# shield.net
KiCad netlist of a schematic drawn in EAGLE
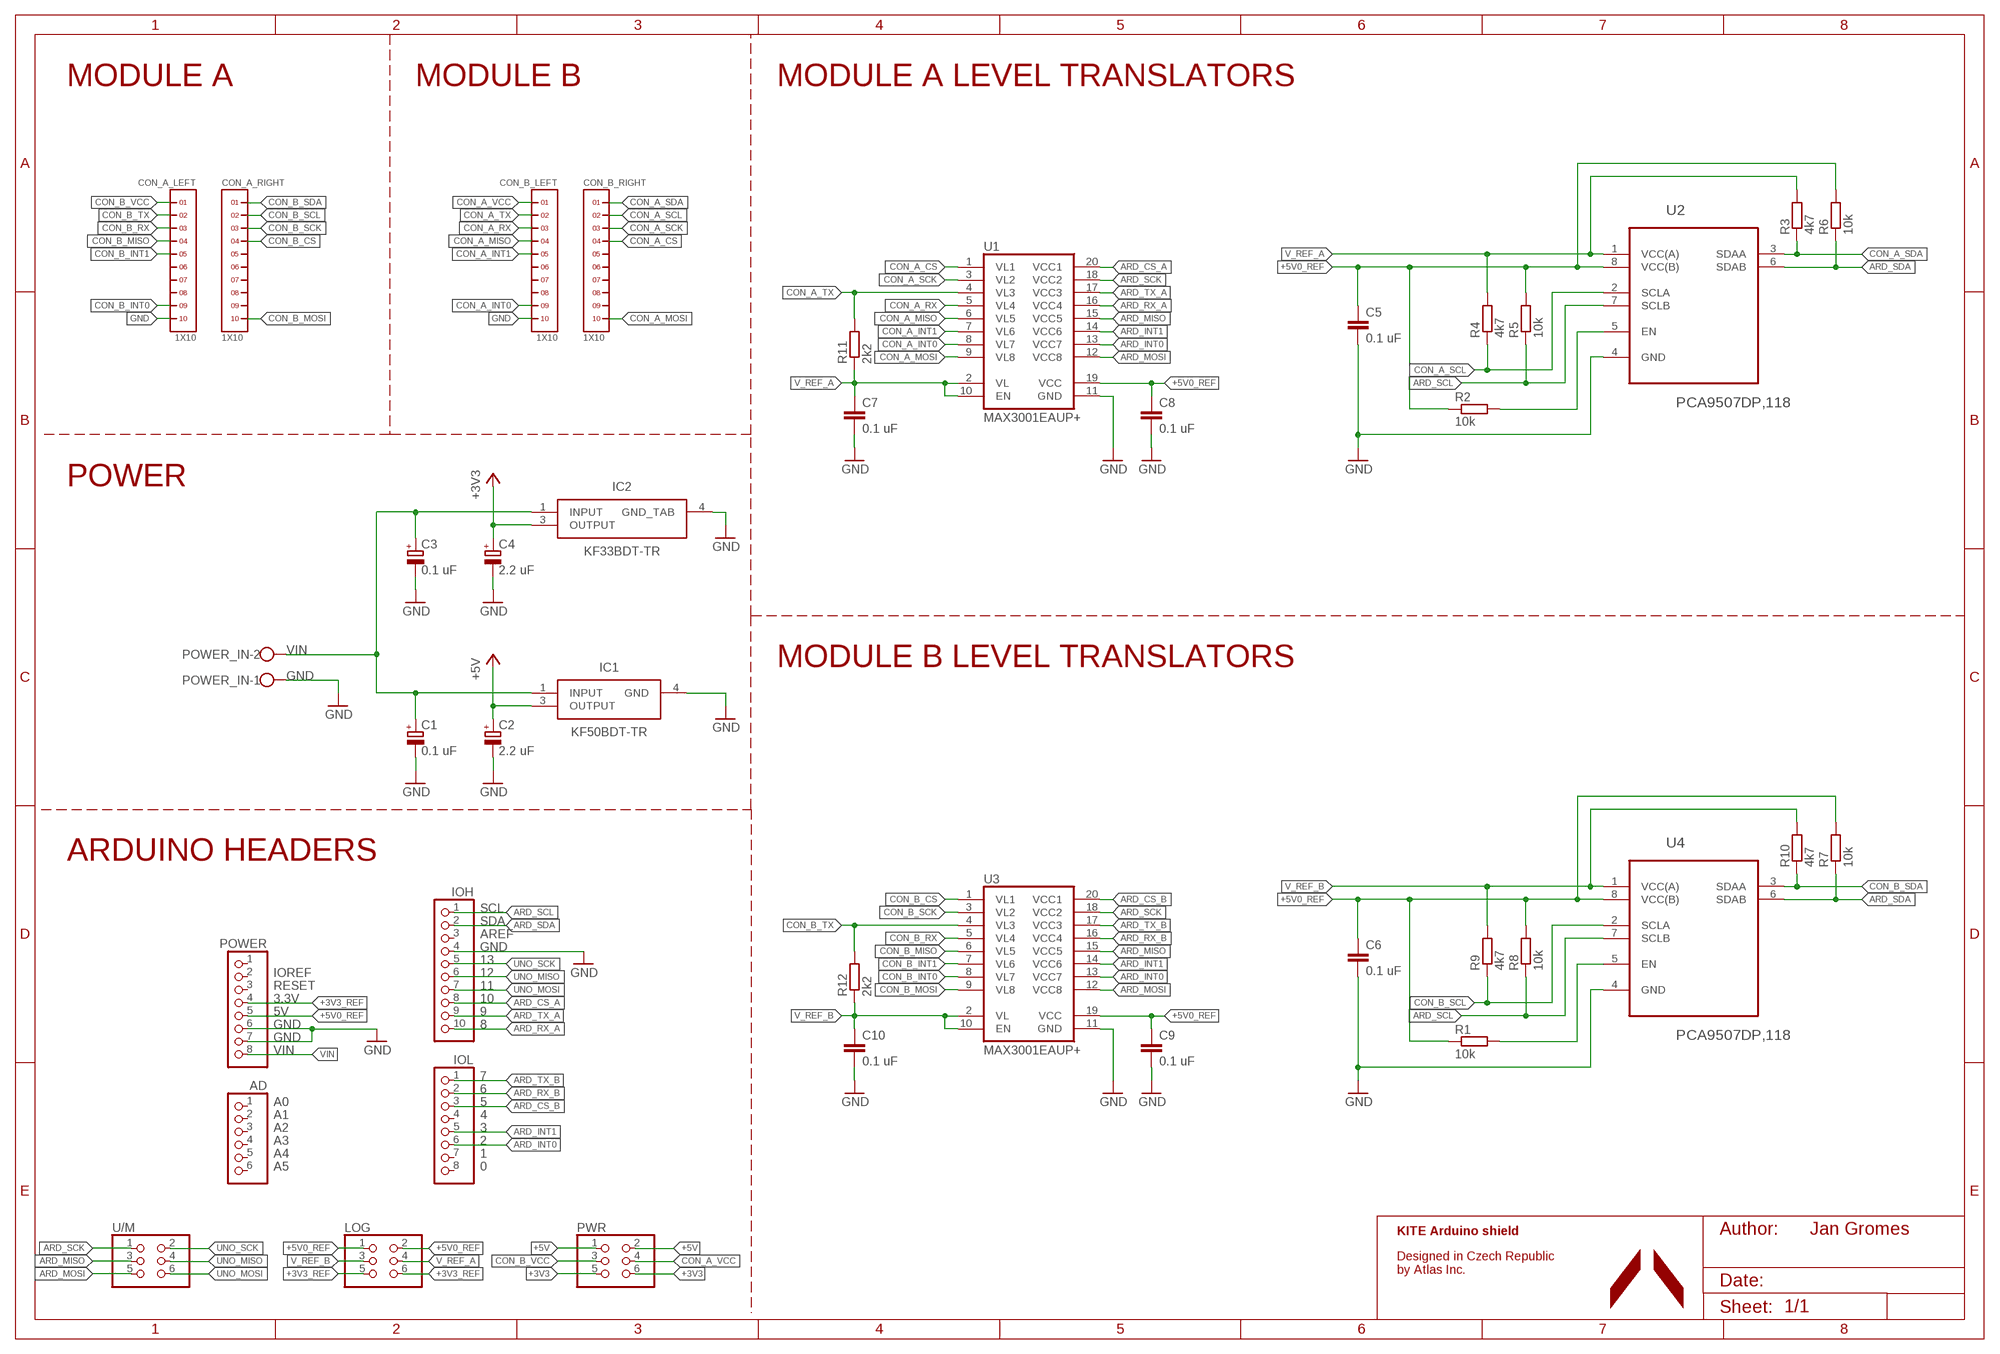
[diagram p0: schematic, sheet 1]

(export (version "E")
  (design (tool "Eeschema 10.0.6"))
  (components
    (comp (ref "AD")
      (value "PINHD-1X6")
      (footprint "eagle-import:1X06")
      (libsource (lib "eagle-import") (part "PINHD-1X6"))
    )
    (comp (ref "C1")
      (value "0.1 uF")
      (footprint "eagle-import:SMC_A")
      (libsource (lib "eagle-import") (part "CPOL-EUSMCA"))
    )
    (comp (ref "C2")
      (value "2.2 uF")
      (footprint "eagle-import:SMC_A")
      (libsource (lib "eagle-import") (part "CPOL-EUSMCA"))
    )
    (comp (ref "C3")
      (value "0.1 uF")
      (footprint "eagle-import:SMC_A")
      (libsource (lib "eagle-import") (part "CPOL-EUSMCA"))
    )
    (comp (ref "C4")
      (value "2.2 uF")
      (footprint "eagle-import:SMC_A")
      (libsource (lib "eagle-import") (part "CPOL-EUSMCA"))
    )
    (comp (ref "C5")
      (value "0.1 uF")
      (footprint "eagle-import:C0603")
      (libsource (lib "eagle-import") (part "C-EUC0603"))
    )
    (comp (ref "C6")
      (value "0.1 uF")
      (footprint "eagle-import:C0603")
      (libsource (lib "eagle-import") (part "C-EUC0603"))
    )
    (comp (ref "C7")
      (value "0.1 uF")
      (footprint "eagle-import:C0603")
      (libsource (lib "eagle-import") (part "C-EUC0603"))
    )
    (comp (ref "C8")
      (value "0.1 uF")
      (footprint "eagle-import:C0603")
      (libsource (lib "eagle-import") (part "C-EUC0603"))
    )
    (comp (ref "C9")
      (value "0.1 uF")
      (footprint "eagle-import:C0603")
      (libsource (lib "eagle-import") (part "C-EUC0603"))
    )
    (comp (ref "C10")
      (value "0.1 uF")
      (footprint "eagle-import:C0603")
      (libsource (lib "eagle-import") (part "C-EUC0603"))
    )
    (comp (ref "CON_A_LEFT")
      (value "1X10")
      (footprint "eagle-import:1X10")
      (libsource (lib "eagle-import") (part "1X10"))
    )
    (comp (ref "CON_A_RIGHT")
      (value "1X10")
      (footprint "eagle-import:1X10")
      (libsource (lib "eagle-import") (part "1X10"))
    )
    (comp (ref "CON_B_LEFT")
      (value "1X10")
      (footprint "eagle-import:1X10")
      (libsource (lib "eagle-import") (part "1X10"))
    )
    (comp (ref "CON_B_RIGHT")
      (value "1X10")
      (footprint "eagle-import:1X10")
      (libsource (lib "eagle-import") (part "1X10"))
    )
    (comp (ref "IC1")
      (value "KF50BDT-TR")
      (footprint "eagle-import:TO228P972X240-3N")
      (fields (field (name "RS_PART_NUMBER") "7140619"))
      (libsource (lib "eagle-import") (part "KF50BDT-TR"))
    )
    (comp (ref "IC2")
      (value "KF33BDT-TR")
      (footprint "eagle-import:TO228P972X240-3N")
      (fields (field (name "RS_PART_NUMBER") "7140616"))
      (libsource (lib "eagle-import") (part "KF33BDT-TR"))
    )
    (comp (ref "IOH")
      (value "PINHD-1X10")
      (footprint "eagle-import:1X10")
      (libsource (lib "eagle-import") (part "PINHD-1X10"))
    )
    (comp (ref "IOL")
      (value "PINHD-1X8")
      (footprint "eagle-import:1X08")
      (libsource (lib "eagle-import") (part "PINHD-1X8"))
    )
    (comp (ref "LOG")
      (value "PINHD-2X3")
      (footprint "eagle-import:2X03")
      (libsource (lib "eagle-import") (part "PINHD-2X3"))
    )
    (comp (ref "POWER")
      (value "PINHD-1X8")
      (footprint "eagle-import:1X08")
      (libsource (lib "eagle-import") (part "PINHD-1X8"))
    )
    (comp (ref "POWER_IN")
      (value "W237-102")
      (footprint "eagle-import:W237-102")
      (fields (field (name "MPN") "237-102"))
      (libsource (lib "eagle-import") (part "W237-102"))
    )
    (comp (ref "PWR")
      (value "PINHD-2X3")
      (footprint "eagle-import:2X03")
      (libsource (lib "eagle-import") (part "PINHD-2X3"))
    )
    (comp (ref "R1")
      (value "10k")
      (footprint "eagle-import:R0603")
      (libsource (lib "eagle-import") (part "R-EU_R0603"))
    )
    (comp (ref "R2")
      (value "10k")
      (footprint "eagle-import:R0603")
      (libsource (lib "eagle-import") (part "R-EU_R0603"))
    )
    (comp (ref "R3")
      (value "4k7")
      (footprint "eagle-import:R0603")
      (libsource (lib "eagle-import") (part "R-EU_R0603"))
    )
    (comp (ref "R4")
      (value "4k7")
      (footprint "eagle-import:R0603")
      (libsource (lib "eagle-import") (part "R-EU_R0603"))
    )
    (comp (ref "R5")
      (value "10k")
      (footprint "eagle-import:R0603")
      (libsource (lib "eagle-import") (part "R-EU_R0603"))
    )
    (comp (ref "R6")
      (value "10k")
      (footprint "eagle-import:R0603")
      (libsource (lib "eagle-import") (part "R-EU_R0603"))
    )
    (comp (ref "R7")
      (value "10k")
      (footprint "eagle-import:R0603")
      (libsource (lib "eagle-import") (part "R-EU_R0603"))
    )
    (comp (ref "R8")
      (value "10k")
      (footprint "eagle-import:R0603")
      (libsource (lib "eagle-import") (part "R-EU_R0603"))
    )
    (comp (ref "R9")
      (value "4k7")
      (footprint "eagle-import:R0603")
      (libsource (lib "eagle-import") (part "R-EU_R0603"))
    )
    (comp (ref "R10")
      (value "4k7")
      (footprint "eagle-import:R0603")
      (libsource (lib "eagle-import") (part "R-EU_R0603"))
    )
    (comp (ref "R11")
      (value "2k2")
      (footprint "eagle-import:R0603")
      (libsource (lib "eagle-import") (part "R-EU_R0603"))
    )
    (comp (ref "R12")
      (value "2k2")
      (footprint "eagle-import:R0603")
      (libsource (lib "eagle-import") (part "R-EU_R0603"))
    )
    (comp (ref "U/M")
      (value "PINHD-2X3")
      (footprint "eagle-import:2X03")
      (libsource (lib "eagle-import") (part "PINHD-2X3"))
    )
    (comp (ref "U1")
      (value "MAX3001EAUP+")
      (footprint "eagle-import:TSSOP20")
      (libsource (lib "eagle-import") (part "MAX3001"))
    )
    (comp (ref "U2")
      (value "PCA9507DP,118")
      (footprint "eagle-import:SOP65P490X110-8N")
      (libsource (lib "eagle-import") (part "PCA9507DP,118"))
    )
    (comp (ref "U3")
      (value "MAX3001EAUP+")
      (footprint "eagle-import:TSSOP20")
      (libsource (lib "eagle-import") (part "MAX3001"))
    )
    (comp (ref "U4")
      (value "PCA9507DP,118")
      (footprint "eagle-import:SOP65P490X110-8N")
      (libsource (lib "eagle-import") (part "PCA9507DP,118"))
    )
  )
  (nets
    (net (code "1") (name "+3V3") (class "Default")
      (node (ref "C4") (pin "+") (pinfunction "+_+") (pintype "passive"))
      (node (ref "IC2") (pin "3") (pinfunction "OUTPUT_3") (pintype "output"))
      (node (ref "PWR") (pin "5") (pinfunction "5_5") (pintype "passive"))
      (node (ref "PWR") (pin "6") (pinfunction "6_6") (pintype "passive"))
    )
    (net (code "2") (name "+3V3_REF") (class "Default")
      (node (ref "LOG") (pin "5") (pinfunction "5_5") (pintype "passive"))
      (node (ref "LOG") (pin "6") (pinfunction "6_6") (pintype "passive"))
      (node (ref "POWER") (pin "4") (pinfunction "4_4") (pintype "passive"))
    )
    (net (code "3") (name "+5V") (class "Default")
      (node (ref "C2") (pin "+") (pinfunction "+_+") (pintype "passive"))
      (node (ref "IC1") (pin "3") (pinfunction "OUTPUT_3") (pintype "power_in"))
      (node (ref "PWR") (pin "1") (pinfunction "1_1") (pintype "passive"))
      (node (ref "PWR") (pin "2") (pinfunction "2_2") (pintype "passive"))
    )
    (net (code "4") (name "+5V0_REF") (class "Default")
      (node (ref "C5") (pin "1") (pinfunction "1_1") (pintype "passive"))
      (node (ref "C6") (pin "1") (pinfunction "1_1") (pintype "passive"))
      (node (ref "C8") (pin "1") (pinfunction "1_1") (pintype "passive"))
      (node (ref "C9") (pin "1") (pinfunction "1_1") (pintype "passive"))
      (node (ref "LOG") (pin "1") (pinfunction "1_1") (pintype "passive"))
      (node (ref "LOG") (pin "2") (pinfunction "2_2") (pintype "passive"))
      (node (ref "POWER") (pin "5") (pinfunction "5_5") (pintype "passive"))
      (node (ref "R1") (pin "1") (pinfunction "1_1") (pintype "passive"))
      (node (ref "R2") (pin "1") (pinfunction "1_1") (pintype "passive"))
      (node (ref "R5") (pin "2") (pinfunction "2_2") (pintype "passive"))
      (node (ref "R6") (pin "2") (pinfunction "2_2") (pintype "passive"))
      (node (ref "R7") (pin "2") (pinfunction "2_2") (pintype "passive"))
      (node (ref "R8") (pin "2") (pinfunction "2_2") (pintype "passive"))
      (node (ref "U1") (pin "19") (pinfunction "VCC_19") (pintype "power_in"))
      (node (ref "U2") (pin "8") (pinfunction "VCC(B)_8") (pintype "power_in"))
      (node (ref "U3") (pin "19") (pinfunction "VCC_19") (pintype "power_in"))
      (node (ref "U4") (pin "8") (pinfunction "VCC(B)_8") (pintype "power_in"))
    )
    (net (code "5") (name "ARD_CS_A") (class "Default")
      (node (ref "IOH") (pin "8") (pinfunction "8_8") (pintype "passive"))
      (node (ref "U1") (pin "20") (pinfunction "VCC1_20") (pintype "bidirectional"))
    )
    (net (code "6") (name "ARD_CS_B") (class "Default")
      (node (ref "IOL") (pin "3") (pinfunction "3_3") (pintype "passive"))
      (node (ref "U3") (pin "20") (pinfunction "VCC1_20") (pintype "bidirectional"))
    )
    (net (code "7") (name "ARD_INT0") (class "Default")
      (node (ref "IOL") (pin "6") (pinfunction "6_6") (pintype "passive"))
      (node (ref "U1") (pin "13") (pinfunction "VCC7_13") (pintype "bidirectional"))
      (node (ref "U3") (pin "13") (pinfunction "VCC7_13") (pintype "bidirectional"))
    )
    (net (code "8") (name "ARD_INT1") (class "Default")
      (node (ref "IOL") (pin "5") (pinfunction "5_5") (pintype "passive"))
      (node (ref "U1") (pin "14") (pinfunction "VCC6_14") (pintype "bidirectional"))
      (node (ref "U3") (pin "14") (pinfunction "VCC6_14") (pintype "bidirectional"))
    )
    (net (code "9") (name "ARD_MISO") (class "Default")
      (node (ref "U/M") (pin "3") (pinfunction "3_3") (pintype "passive"))
      (node (ref "U1") (pin "15") (pinfunction "VCC5_15") (pintype "bidirectional"))
      (node (ref "U3") (pin "15") (pinfunction "VCC5_15") (pintype "bidirectional"))
    )
    (net (code "10") (name "ARD_MOSI") (class "Default")
      (node (ref "U/M") (pin "5") (pinfunction "5_5") (pintype "passive"))
      (node (ref "U1") (pin "12") (pinfunction "VCC8_12") (pintype "bidirectional"))
      (node (ref "U3") (pin "12") (pinfunction "VCC8_12") (pintype "bidirectional"))
    )
    (net (code "11") (name "ARD_RX_A") (class "Default")
      (node (ref "IOH") (pin "10") (pinfunction "10_10") (pintype "passive"))
      (node (ref "U1") (pin "16") (pinfunction "VCC4_16") (pintype "bidirectional"))
    )
    (net (code "12") (name "ARD_RX_B") (class "Default")
      (node (ref "IOL") (pin "2") (pinfunction "2_2") (pintype "passive"))
      (node (ref "U3") (pin "16") (pinfunction "VCC4_16") (pintype "bidirectional"))
    )
    (net (code "13") (name "ARD_SCK") (class "Default")
      (node (ref "U/M") (pin "1") (pinfunction "1_1") (pintype "passive"))
      (node (ref "U1") (pin "18") (pinfunction "VCC2_18") (pintype "bidirectional"))
      (node (ref "U3") (pin "18") (pinfunction "VCC2_18") (pintype "bidirectional"))
    )
    (net (code "14") (name "ARD_SCL") (class "Default")
      (node (ref "IOH") (pin "1") (pinfunction "1_1") (pintype "passive"))
      (node (ref "R5") (pin "1") (pinfunction "1_1") (pintype "passive"))
      (node (ref "R8") (pin "1") (pinfunction "1_1") (pintype "passive"))
      (node (ref "U2") (pin "7") (pinfunction "SCLB_7") (pintype "input"))
      (node (ref "U4") (pin "7") (pinfunction "SCLB_7") (pintype "input"))
    )
    (net (code "15") (name "ARD_SDA") (class "Default")
      (node (ref "IOH") (pin "2") (pinfunction "2_2") (pintype "passive"))
      (node (ref "R6") (pin "1") (pinfunction "1_1") (pintype "passive"))
      (node (ref "R7") (pin "1") (pinfunction "1_1") (pintype "passive"))
      (node (ref "U2") (pin "6") (pinfunction "SDAB_6") (pintype "bidirectional"))
      (node (ref "U4") (pin "6") (pinfunction "SDAB_6") (pintype "bidirectional"))
    )
    (net (code "16") (name "ARD_TX_A") (class "Default")
      (node (ref "IOH") (pin "9") (pinfunction "9_9") (pintype "passive"))
      (node (ref "U1") (pin "17") (pinfunction "VCC3_17") (pintype "bidirectional"))
    )
    (net (code "17") (name "ARD_TX_B") (class "Default")
      (node (ref "IOL") (pin "1") (pinfunction "1_1") (pintype "passive"))
      (node (ref "U3") (pin "17") (pinfunction "VCC3_17") (pintype "bidirectional"))
    )
    (net (code "18") (name "CON_A_CS") (class "Default")
      (node (ref "CON_B_RIGHT") (pin "4") (pinfunction "4_4") (pintype "bidirectional"))
      (node (ref "U1") (pin "1") (pinfunction "VL1_1") (pintype "bidirectional"))
    )
    (net (code "19") (name "CON_A_INT0") (class "Default")
      (node (ref "CON_B_LEFT") (pin "9") (pinfunction "9_9") (pintype "bidirectional"))
      (node (ref "U1") (pin "8") (pinfunction "VL7_8") (pintype "bidirectional"))
    )
    (net (code "20") (name "CON_A_INT1") (class "Default")
      (node (ref "CON_B_LEFT") (pin "5") (pinfunction "5_5") (pintype "bidirectional"))
      (node (ref "U1") (pin "7") (pinfunction "VL6_7") (pintype "bidirectional"))
    )
    (net (code "21") (name "CON_A_MISO") (class "Default")
      (node (ref "CON_B_LEFT") (pin "4") (pinfunction "4_4") (pintype "bidirectional"))
      (node (ref "U1") (pin "6") (pinfunction "VL5_6") (pintype "bidirectional"))
    )
    (net (code "22") (name "CON_A_MOSI") (class "Default")
      (node (ref "CON_B_RIGHT") (pin "10") (pinfunction "10_10") (pintype "bidirectional"))
      (node (ref "U1") (pin "9") (pinfunction "VL8_9") (pintype "bidirectional"))
    )
    (net (code "23") (name "CON_A_RX") (class "Default")
      (node (ref "CON_B_LEFT") (pin "3") (pinfunction "3_3") (pintype "bidirectional"))
      (node (ref "U1") (pin "5") (pinfunction "VL4_5") (pintype "bidirectional"))
    )
    (net (code "24") (name "CON_A_SCK") (class "Default")
      (node (ref "CON_B_RIGHT") (pin "3") (pinfunction "3_3") (pintype "bidirectional"))
      (node (ref "U1") (pin "3") (pinfunction "VL2_3") (pintype "bidirectional"))
    )
    (net (code "25") (name "CON_A_SCL") (class "Default")
      (node (ref "CON_B_RIGHT") (pin "2") (pinfunction "2_2") (pintype "bidirectional"))
      (node (ref "R4") (pin "1") (pinfunction "1_1") (pintype "passive"))
      (node (ref "U2") (pin "2") (pinfunction "SCLA_2") (pintype "input"))
    )
    (net (code "26") (name "CON_A_SDA") (class "Default")
      (node (ref "CON_B_RIGHT") (pin "1") (pinfunction "1_1") (pintype "bidirectional"))
      (node (ref "R3") (pin "1") (pinfunction "1_1") (pintype "passive"))
      (node (ref "U2") (pin "3") (pinfunction "SDAA_3") (pintype "bidirectional"))
    )
    (net (code "27") (name "CON_A_TX") (class "Default")
      (node (ref "CON_B_LEFT") (pin "2") (pinfunction "2_2") (pintype "bidirectional"))
      (node (ref "R11") (pin "2") (pinfunction "2_2") (pintype "passive"))
      (node (ref "U1") (pin "4") (pinfunction "VL3_4") (pintype "bidirectional"))
    )
    (net (code "28") (name "CON_A_VCC") (class "Default")
      (node (ref "CON_B_LEFT") (pin "1") (pinfunction "1_1") (pintype "bidirectional"))
      (node (ref "PWR") (pin "4") (pinfunction "4_4") (pintype "passive"))
    )
    (net (code "29") (name "CON_B_CS") (class "Default")
      (node (ref "CON_A_RIGHT") (pin "4") (pinfunction "4_4") (pintype "bidirectional"))
      (node (ref "U3") (pin "1") (pinfunction "VL1_1") (pintype "bidirectional"))
    )
    (net (code "30") (name "CON_B_INT0") (class "Default")
      (node (ref "CON_A_LEFT") (pin "9") (pinfunction "9_9") (pintype "bidirectional"))
      (node (ref "U3") (pin "8") (pinfunction "VL7_8") (pintype "bidirectional"))
    )
    (net (code "31") (name "CON_B_INT1") (class "Default")
      (node (ref "CON_A_LEFT") (pin "5") (pinfunction "5_5") (pintype "bidirectional"))
      (node (ref "U3") (pin "7") (pinfunction "VL6_7") (pintype "bidirectional"))
    )
    (net (code "32") (name "CON_B_MISO") (class "Default")
      (node (ref "CON_A_LEFT") (pin "4") (pinfunction "4_4") (pintype "bidirectional"))
      (node (ref "U3") (pin "6") (pinfunction "VL5_6") (pintype "bidirectional"))
    )
    (net (code "33") (name "CON_B_MOSI") (class "Default")
      (node (ref "CON_A_RIGHT") (pin "10") (pinfunction "10_10") (pintype "bidirectional"))
      (node (ref "U3") (pin "9") (pinfunction "VL8_9") (pintype "bidirectional"))
    )
    (net (code "34") (name "CON_B_RX") (class "Default")
      (node (ref "CON_A_LEFT") (pin "3") (pinfunction "3_3") (pintype "bidirectional"))
      (node (ref "U3") (pin "5") (pinfunction "VL4_5") (pintype "bidirectional"))
    )
    (net (code "35") (name "CON_B_SCK") (class "Default")
      (node (ref "CON_A_RIGHT") (pin "3") (pinfunction "3_3") (pintype "bidirectional"))
      (node (ref "U3") (pin "3") (pinfunction "VL2_3") (pintype "bidirectional"))
    )
    (net (code "36") (name "CON_B_SCL") (class "Default")
      (node (ref "CON_A_RIGHT") (pin "2") (pinfunction "2_2") (pintype "bidirectional"))
      (node (ref "R9") (pin "1") (pinfunction "1_1") (pintype "passive"))
      (node (ref "U4") (pin "2") (pinfunction "SCLA_2") (pintype "input"))
    )
    (net (code "37") (name "CON_B_SDA") (class "Default")
      (node (ref "CON_A_RIGHT") (pin "1") (pinfunction "1_1") (pintype "bidirectional"))
      (node (ref "R10") (pin "1") (pinfunction "1_1") (pintype "passive"))
      (node (ref "U4") (pin "3") (pinfunction "SDAA_3") (pintype "bidirectional"))
    )
    (net (code "38") (name "CON_B_TX") (class "Default")
      (node (ref "CON_A_LEFT") (pin "2") (pinfunction "2_2") (pintype "bidirectional"))
      (node (ref "R12") (pin "2") (pinfunction "2_2") (pintype "passive"))
      (node (ref "U3") (pin "4") (pinfunction "VL3_4") (pintype "bidirectional"))
    )
    (net (code "39") (name "CON_B_VCC") (class "Default")
      (node (ref "CON_A_LEFT") (pin "1") (pinfunction "1_1") (pintype "bidirectional"))
      (node (ref "PWR") (pin "3") (pinfunction "3_3") (pintype "passive"))
    )
    (net (code "40") (name "GND") (class "Default")
      (node (ref "C1") (pin "-") (pinfunction "-_-") (pintype "passive"))
      (node (ref "C10") (pin "2") (pinfunction "2_2") (pintype "passive"))
      (node (ref "C2") (pin "-") (pinfunction "-_-") (pintype "passive"))
      (node (ref "C3") (pin "-") (pinfunction "-_-") (pintype "passive"))
      (node (ref "C4") (pin "-") (pinfunction "-_-") (pintype "passive"))
      (node (ref "C5") (pin "2") (pinfunction "2_2") (pintype "passive"))
      (node (ref "C6") (pin "2") (pinfunction "2_2") (pintype "passive"))
      (node (ref "C7") (pin "2") (pinfunction "2_2") (pintype "passive"))
      (node (ref "C8") (pin "2") (pinfunction "2_2") (pintype "passive"))
      (node (ref "C9") (pin "2") (pinfunction "2_2") (pintype "passive"))
      (node (ref "CON_A_LEFT") (pin "10") (pinfunction "10_10") (pintype "bidirectional"))
      (node (ref "CON_B_LEFT") (pin "10") (pinfunction "10_10") (pintype "bidirectional"))
      (node (ref "IC1") (pin "4") (pinfunction "GND_4") (pintype "input"))
      (node (ref "IC2") (pin "4") (pinfunction "GND_TAB_4") (pintype "power_in"))
      (node (ref "IOH") (pin "4") (pinfunction "4_4") (pintype "passive"))
      (node (ref "POWER") (pin "6") (pinfunction "6_6") (pintype "passive"))
      (node (ref "POWER") (pin "7") (pinfunction "7_7") (pintype "passive"))
      (node (ref "POWER_IN") (pin "1") (pinfunction "KL_1") (pintype "passive"))
      (node (ref "U1") (pin "11") (pinfunction "GND_11") (pintype "power_in"))
      (node (ref "U2") (pin "4") (pinfunction "GND_4") (pintype "passive"))
      (node (ref "U3") (pin "11") (pinfunction "GND_11") (pintype "power_in"))
      (node (ref "U4") (pin "4") (pinfunction "GND_4") (pintype "passive"))
    )
    (net (code "41") (name "Net-(U2-EN)") (class "Default")
      (node (ref "R2") (pin "2") (pinfunction "2_2") (pintype "passive"))
      (node (ref "U2") (pin "5") (pinfunction "EN_5") (pintype "input"))
    )
    (net (code "42") (name "Net-(U4-EN)") (class "Default")
      (node (ref "R1") (pin "2") (pinfunction "2_2") (pintype "passive"))
      (node (ref "U4") (pin "5") (pinfunction "EN_5") (pintype "input"))
    )
    (net (code "43") (name "UNO_MISO") (class "Default")
      (node (ref "IOH") (pin "6") (pinfunction "6_6") (pintype "passive"))
      (node (ref "U/M") (pin "4") (pinfunction "4_4") (pintype "passive"))
    )
    (net (code "44") (name "UNO_MOSI") (class "Default")
      (node (ref "IOH") (pin "7") (pinfunction "7_7") (pintype "passive"))
      (node (ref "U/M") (pin "6") (pinfunction "6_6") (pintype "passive"))
    )
    (net (code "45") (name "UNO_SCK") (class "Default")
      (node (ref "IOH") (pin "5") (pinfunction "5_5") (pintype "passive"))
      (node (ref "U/M") (pin "2") (pinfunction "2_2") (pintype "passive"))
    )
    (net (code "46") (name "VIN") (class "Default")
      (node (ref "C1") (pin "+") (pinfunction "+_+") (pintype "passive"))
      (node (ref "C3") (pin "+") (pinfunction "+_+") (pintype "passive"))
      (node (ref "IC1") (pin "1") (pinfunction "INPUT_1") (pintype "output"))
      (node (ref "IC2") (pin "1") (pinfunction "INPUT_1") (pintype "input"))
      (node (ref "POWER") (pin "8") (pinfunction "8_8") (pintype "passive"))
      (node (ref "POWER_IN") (pin "2") (pinfunction "KL_2") (pintype "passive"))
    )
    (net (code "47") (name "V_REF_A") (class "Default")
      (node (ref "C7") (pin "1") (pinfunction "1_1") (pintype "passive"))
      (node (ref "LOG") (pin "4") (pinfunction "4_4") (pintype "passive"))
      (node (ref "R11") (pin "1") (pinfunction "1_1") (pintype "passive"))
      (node (ref "R3") (pin "2") (pinfunction "2_2") (pintype "passive"))
      (node (ref "R4") (pin "2") (pinfunction "2_2") (pintype "passive"))
      (node (ref "U1") (pin "10") (pinfunction "EN_10") (pintype "power_in"))
      (node (ref "U1") (pin "2") (pinfunction "VL_2") (pintype "input"))
      (node (ref "U2") (pin "1") (pinfunction "VCC(A)_1") (pintype "power_in"))
    )
    (net (code "48") (name "V_REF_B") (class "Default")
      (node (ref "C10") (pin "1") (pinfunction "1_1") (pintype "passive"))
      (node (ref "LOG") (pin "3") (pinfunction "3_3") (pintype "passive"))
      (node (ref "R10") (pin "2") (pinfunction "2_2") (pintype "passive"))
      (node (ref "R12") (pin "1") (pinfunction "1_1") (pintype "passive"))
      (node (ref "R9") (pin "2") (pinfunction "2_2") (pintype "passive"))
      (node (ref "U3") (pin "10") (pinfunction "EN_10") (pintype "power_in"))
      (node (ref "U3") (pin "2") (pinfunction "VL_2") (pintype "input"))
      (node (ref "U4") (pin "1") (pinfunction "VCC(A)_1") (pintype "power_in"))
    )
    (net (code "49") (name "unconnected-(AD-Pad1)") (class "Default")
      (node (ref "AD") (pin "1") (pinfunction "1_1") (pintype "passive"))
    )
    (net (code "50") (name "unconnected-(AD-Pad2)") (class "Default")
      (node (ref "AD") (pin "2") (pinfunction "2_2") (pintype "passive"))
    )
    (net (code "51") (name "unconnected-(AD-Pad3)") (class "Default")
      (node (ref "AD") (pin "3") (pinfunction "3_3") (pintype "passive"))
    )
    (net (code "52") (name "unconnected-(AD-Pad4)") (class "Default")
      (node (ref "AD") (pin "4") (pinfunction "4_4") (pintype "passive"))
    )
    (net (code "53") (name "unconnected-(AD-Pad5)") (class "Default")
      (node (ref "AD") (pin "5") (pinfunction "5_5") (pintype "passive"))
    )
    (net (code "54") (name "unconnected-(AD-Pad6)") (class "Default")
      (node (ref "AD") (pin "6") (pinfunction "6_6") (pintype "passive"))
    )
    (net (code "55") (name "unconnected-(CON_A_LEFT-Pad6)") (class "Default")
      (node (ref "CON_A_LEFT") (pin "6") (pinfunction "6_6") (pintype "bidirectional"))
    )
    (net (code "56") (name "unconnected-(CON_A_LEFT-Pad7)") (class "Default")
      (node (ref "CON_A_LEFT") (pin "7") (pinfunction "7_7") (pintype "bidirectional"))
    )
    (net (code "57") (name "unconnected-(CON_A_LEFT-Pad8)") (class "Default")
      (node (ref "CON_A_LEFT") (pin "8") (pinfunction "8_8") (pintype "bidirectional"))
    )
    (net (code "58") (name "unconnected-(CON_A_RIGHT-Pad5)") (class "Default")
      (node (ref "CON_A_RIGHT") (pin "5") (pinfunction "5_5") (pintype "bidirectional"))
    )
    (net (code "59") (name "unconnected-(CON_A_RIGHT-Pad6)") (class "Default")
      (node (ref "CON_A_RIGHT") (pin "6") (pinfunction "6_6") (pintype "bidirectional"))
    )
    (net (code "60") (name "unconnected-(CON_A_RIGHT-Pad7)") (class "Default")
      (node (ref "CON_A_RIGHT") (pin "7") (pinfunction "7_7") (pintype "bidirectional"))
    )
    (net (code "61") (name "unconnected-(CON_A_RIGHT-Pad8)") (class "Default")
      (node (ref "CON_A_RIGHT") (pin "8") (pinfunction "8_8") (pintype "bidirectional"))
    )
    (net (code "62") (name "unconnected-(CON_A_RIGHT-Pad9)") (class "Default")
      (node (ref "CON_A_RIGHT") (pin "9") (pinfunction "9_9") (pintype "bidirectional"))
    )
    (net (code "63") (name "unconnected-(CON_B_LEFT-Pad6)") (class "Default")
      (node (ref "CON_B_LEFT") (pin "6") (pinfunction "6_6") (pintype "bidirectional"))
    )
    (net (code "64") (name "unconnected-(CON_B_LEFT-Pad7)") (class "Default")
      (node (ref "CON_B_LEFT") (pin "7") (pinfunction "7_7") (pintype "bidirectional"))
    )
    (net (code "65") (name "unconnected-(CON_B_LEFT-Pad8)") (class "Default")
      (node (ref "CON_B_LEFT") (pin "8") (pinfunction "8_8") (pintype "bidirectional"))
    )
    (net (code "66") (name "unconnected-(CON_B_RIGHT-Pad5)") (class "Default")
      (node (ref "CON_B_RIGHT") (pin "5") (pinfunction "5_5") (pintype "bidirectional"))
    )
    (net (code "67") (name "unconnected-(CON_B_RIGHT-Pad6)") (class "Default")
      (node (ref "CON_B_RIGHT") (pin "6") (pinfunction "6_6") (pintype "bidirectional"))
    )
    (net (code "68") (name "unconnected-(CON_B_RIGHT-Pad7)") (class "Default")
      (node (ref "CON_B_RIGHT") (pin "7") (pinfunction "7_7") (pintype "bidirectional"))
    )
    (net (code "69") (name "unconnected-(CON_B_RIGHT-Pad8)") (class "Default")
      (node (ref "CON_B_RIGHT") (pin "8") (pinfunction "8_8") (pintype "bidirectional"))
    )
    (net (code "70") (name "unconnected-(CON_B_RIGHT-Pad9)") (class "Default")
      (node (ref "CON_B_RIGHT") (pin "9") (pinfunction "9_9") (pintype "bidirectional"))
    )
    (net (code "71") (name "unconnected-(IOH-Pad3)") (class "Default")
      (node (ref "IOH") (pin "3") (pinfunction "3_3") (pintype "passive"))
    )
    (net (code "72") (name "unconnected-(IOL-Pad4)") (class "Default")
      (node (ref "IOL") (pin "4") (pinfunction "4_4") (pintype "passive"))
    )
    (net (code "73") (name "unconnected-(IOL-Pad7)") (class "Default")
      (node (ref "IOL") (pin "7") (pinfunction "7_7") (pintype "passive"))
    )
    (net (code "74") (name "unconnected-(IOL-Pad8)") (class "Default")
      (node (ref "IOL") (pin "8") (pinfunction "8_8") (pintype "passive"))
    )
    (net (code "75") (name "unconnected-(POWER-Pad1)") (class "Default")
      (node (ref "POWER") (pin "1") (pinfunction "1_1") (pintype "passive"))
    )
    (net (code "76") (name "unconnected-(POWER-Pad2)") (class "Default")
      (node (ref "POWER") (pin "2") (pinfunction "2_2") (pintype "passive"))
    )
    (net (code "77") (name "unconnected-(POWER-Pad3)") (class "Default")
      (node (ref "POWER") (pin "3") (pinfunction "3_3") (pintype "passive"))
    )
  )
)
